# LineSensors.net
KiCad netlist of a schematic drawn in Altium Designer
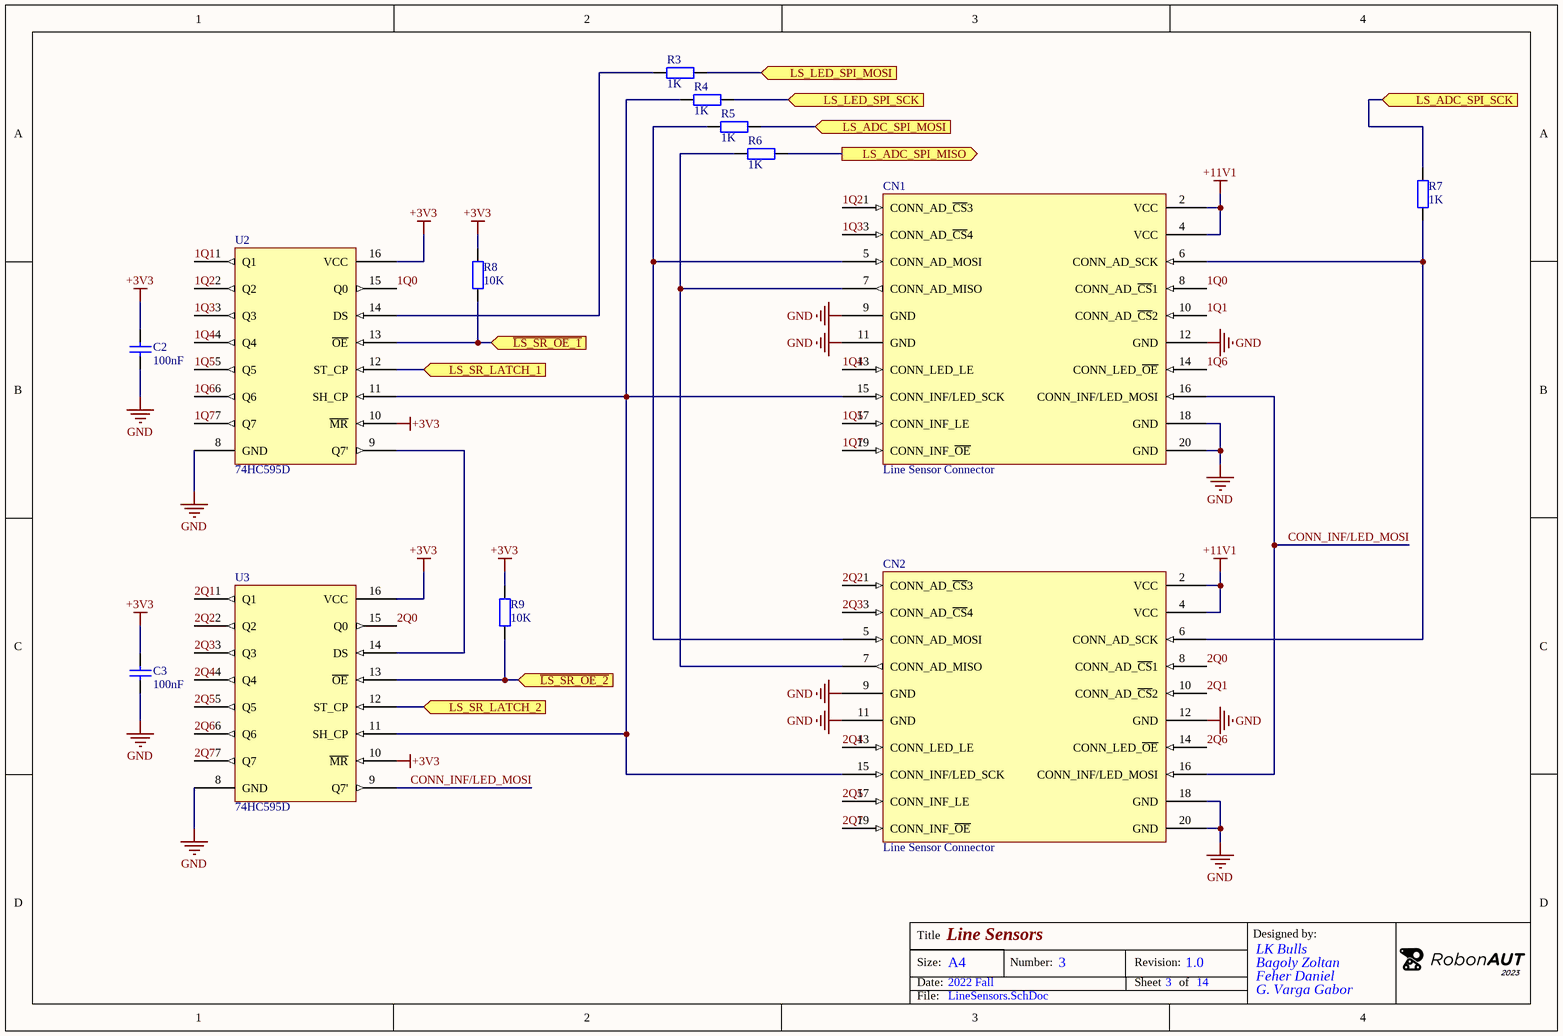
[diagram p0: LineSensors.SchDoc]

(export (version "E")
  (design (tool "Eeschema 10.0.6"))
  (components
    (comp (ref "C2")
      (value "100nF")
      (footprint "FP_0805_CAP_085")
      (description "Capacitor")
      (fields (field (name "TOLERANCE") "10%") (field (name "VOLTAGE") "50V"))
      (libsource (lib "LKBulls2023") (part "CAP"))
    )
    (comp (ref "C3")
      (value "100nF")
      (footprint "FP_0805_CAP_085")
      (description "Capacitor")
      (fields (field (name "TOLERANCE") "10%") (field (name "VOLTAGE") "50V"))
      (libsource (lib "LKBulls2023") (part "CAP"))
    )
    (comp (ref "CN1")
      (value "Line Sensor Connector")
      (footprint "CONNECTOR-20P")
      (libsource (lib "LKBulls2023") (part "Connector_Line_Sensor"))
    )
    (comp (ref "CN2")
      (value "Line Sensor Connector")
      (footprint "CONNECTOR-20P")
      (libsource (lib "LKBulls2023") (part "Connector_Line_Sensor"))
    )
    (comp (ref "R3")
      (value "1K")
      (footprint "FP_0805_RES")
      (description "Resistor")
      (fields (field (name "TOLERANCE") "5%") (field (name "POWER") "0.125W"))
      (libsource (lib "LKBulls2023") (part "RES"))
    )
    (comp (ref "R4")
      (value "1K")
      (footprint "FP_0805_RES")
      (description "Resistor")
      (fields (field (name "TOLERANCE") "5%") (field (name "POWER") "0.125W"))
      (libsource (lib "LKBulls2023") (part "RES"))
    )
    (comp (ref "R5")
      (value "1K")
      (footprint "FP_0805_RES")
      (description "Resistor")
      (fields (field (name "TOLERANCE") "5%") (field (name "POWER") "0.125W"))
      (libsource (lib "LKBulls2023") (part "RES"))
    )
    (comp (ref "R6")
      (value "1K")
      (footprint "FP_0805_RES")
      (description "Resistor")
      (fields (field (name "TOLERANCE") "5%") (field (name "POWER") "0.125W"))
      (libsource (lib "LKBulls2023") (part "RES"))
    )
    (comp (ref "R7")
      (value "1K")
      (footprint "FP_0805_RES")
      (description "Resistor")
      (fields (field (name "TOLERANCE") "5%") (field (name "POWER") "0.125W"))
      (libsource (lib "") (part "RES_1"))
    )
    (comp (ref "R8")
      (value "10K")
      (footprint "FP_0805_RES")
      (description "Resistor")
      (fields (field (name "TOLERANCE") "5%") (field (name "POWER") "0.125W"))
      (libsource (lib "") (part "RES_1"))
    )
    (comp (ref "R9")
      (value "10K")
      (footprint "FP_0805_RES")
      (description "Resistor")
      (fields (field (name "TOLERANCE") "5%") (field (name "POWER") "0.125W"))
      (libsource (lib "") (part "RES_1"))
    )
    (comp (ref "U2")
      (value "74HC595D")
      (footprint "SO16")
      (description "8-bit serial-in, serial or parallel-out shift register with output latches; 3-state")
      (libsource (lib "LKBulls2023") (part "74HC595D"))
    )
    (comp (ref "U3")
      (value "74HC595D")
      (footprint "SO16")
      (description "8-bit serial-in, serial or parallel-out shift register with output latches; 3-state")
      (libsource (lib "LKBulls2023") (part "74HC595D"))
    )
  )
  (nets
    (net (code "1") (name "+3V3") (class "Default")
      (node (ref "C2") (pin "2") (pinfunction "2_2") (pintype "passive"))
      (node (ref "C3") (pin "2") (pinfunction "2_2") (pintype "passive"))
      (node (ref "R8") (pin "2") (pinfunction "2_2") (pintype "passive"))
      (node (ref "R9") (pin "2") (pinfunction "2_2") (pintype "passive"))
      (node (ref "U2") (pin "10") (pinfunction "~{MR}_10") (pintype "input"))
      (node (ref "U2") (pin "16") (pinfunction "VCC_16") (pintype "passive"))
      (node (ref "U3") (pin "10") (pinfunction "~{MR}_10") (pintype "input"))
      (node (ref "U3") (pin "16") (pinfunction "VCC_16") (pintype "passive"))
    )
    (net (code "2") (name "+11V1") (class "Default")
      (node (ref "CN1") (pin "2") (pinfunction "VCC_2") (pintype "power_in"))
      (node (ref "CN1") (pin "4") (pinfunction "VCC_4") (pintype "power_in"))
      (node (ref "CN2") (pin "2") (pinfunction "VCC_2") (pintype "power_in"))
      (node (ref "CN2") (pin "4") (pinfunction "VCC_4") (pintype "power_in"))
    )
    (net (code "3") (name "/1Q0") (class "Default")
      (node (ref "CN1") (pin "8") (pinfunction "CONN_AD_~{CS}1_8") (pintype "input"))
      (node (ref "U2") (pin "15") (pinfunction "Q0_15") (pintype "output"))
    )
    (net (code "4") (name "/1Q1") (class "Default")
      (node (ref "CN1") (pin "10") (pinfunction "CONN_AD_~{CS}2_10") (pintype "input"))
      (node (ref "U2") (pin "1") (pinfunction "Q1_1") (pintype "output"))
    )
    (net (code "5") (name "/1Q2") (class "Default")
      (node (ref "CN1") (pin "1") (pinfunction "CONN_AD_~{CS}3_1") (pintype "input"))
      (node (ref "U2") (pin "2") (pinfunction "Q2_2") (pintype "output"))
    )
    (net (code "6") (name "/1Q3") (class "Default")
      (node (ref "CN1") (pin "3") (pinfunction "CONN_AD_~{CS}4_3") (pintype "input"))
      (node (ref "U2") (pin "3") (pinfunction "Q3_3") (pintype "output"))
    )
    (net (code "7") (name "/1Q4") (class "Default")
      (node (ref "CN1") (pin "13") (pinfunction "CONN_LED_LE_13") (pintype "input"))
      (node (ref "U2") (pin "4") (pinfunction "Q4_4") (pintype "output"))
    )
    (net (code "8") (name "/1Q5") (class "Default")
      (node (ref "CN1") (pin "17") (pinfunction "CONN_INF_LE_17") (pintype "input"))
      (node (ref "U2") (pin "5") (pinfunction "Q5_5") (pintype "output"))
    )
    (net (code "9") (name "/1Q6") (class "Default")
      (node (ref "CN1") (pin "14") (pinfunction "CONN_LED_~{OE}_14") (pintype "input"))
      (node (ref "U2") (pin "6") (pinfunction "Q6_6") (pintype "output"))
    )
    (net (code "10") (name "/1Q7") (class "Default")
      (node (ref "CN1") (pin "19") (pinfunction "CONN_INF_~{OE}_19") (pintype "input"))
      (node (ref "U2") (pin "7") (pinfunction "Q7_7") (pintype "output"))
    )
    (net (code "11") (name "/2Q0") (class "Default")
      (node (ref "CN2") (pin "8") (pinfunction "CONN_AD_~{CS}1_8") (pintype "input"))
      (node (ref "U3") (pin "15") (pinfunction "Q0_15") (pintype "output"))
    )
    (net (code "12") (name "/2Q1") (class "Default")
      (node (ref "CN2") (pin "10") (pinfunction "CONN_AD_~{CS}2_10") (pintype "input"))
      (node (ref "U3") (pin "1") (pinfunction "Q1_1") (pintype "output"))
    )
    (net (code "13") (name "/2Q2") (class "Default")
      (node (ref "CN2") (pin "1") (pinfunction "CONN_AD_~{CS}3_1") (pintype "input"))
      (node (ref "U3") (pin "2") (pinfunction "Q2_2") (pintype "output"))
    )
    (net (code "14") (name "/2Q3") (class "Default")
      (node (ref "CN2") (pin "3") (pinfunction "CONN_AD_~{CS}4_3") (pintype "input"))
      (node (ref "U3") (pin "3") (pinfunction "Q3_3") (pintype "output"))
    )
    (net (code "15") (name "/2Q4") (class "Default")
      (node (ref "CN2") (pin "13") (pinfunction "CONN_LED_LE_13") (pintype "input"))
      (node (ref "U3") (pin "4") (pinfunction "Q4_4") (pintype "output"))
    )
    (net (code "16") (name "/2Q5") (class "Default")
      (node (ref "CN2") (pin "17") (pinfunction "CONN_INF_LE_17") (pintype "input"))
      (node (ref "U3") (pin "5") (pinfunction "Q5_5") (pintype "output"))
    )
    (net (code "17") (name "/2Q6") (class "Default")
      (node (ref "CN2") (pin "14") (pinfunction "CONN_LED_~{OE}_14") (pintype "input"))
      (node (ref "U3") (pin "6") (pinfunction "Q6_6") (pintype "output"))
    )
    (net (code "18") (name "/2Q7") (class "Default")
      (node (ref "CN2") (pin "19") (pinfunction "CONN_INF_~{OE}_19") (pintype "input"))
      (node (ref "U3") (pin "7") (pinfunction "Q7_7") (pintype "output"))
    )
    (net (code "19") (name "/CONN_INF{slash}LED_MOSI") (class "Default")
      (node (ref "CN1") (pin "16") (pinfunction "CONN_INF/LED_MOSI_16") (pintype "input"))
      (node (ref "CN2") (pin "16") (pinfunction "CONN_INF/LED_MOSI_16") (pintype "input"))
      (node (ref "U3") (pin "9") (pinfunction "Q7'_9") (pintype "output"))
    )
    (net (code "20") (name "/LS_ADC_SPI_MISO") (class "Default")
      (node (ref "R6") (pin "2") (pinfunction "2_2") (pintype "passive"))
    )
    (net (code "21") (name "/LS_ADC_SPI_MOSI") (class "Default")
      (node (ref "R5") (pin "2") (pinfunction "2_2") (pintype "passive"))
    )
    (net (code "22") (name "/LS_ADC_SPI_SCK") (class "Default")
      (node (ref "R7") (pin "2") (pinfunction "2_2") (pintype "passive"))
    )
    (net (code "23") (name "/LS_LED_SPI_MOSI") (class "Default")
      (node (ref "R3") (pin "2") (pinfunction "2_2") (pintype "passive"))
    )
    (net (code "24") (name "/LS_LED_SPI_SCK") (class "Default")
      (node (ref "R4") (pin "2") (pinfunction "2_2") (pintype "passive"))
    )
    (net (code "25") (name "/LS_SR_LATCH_1") (class "Default")
      (node (ref "U2") (pin "12") (pinfunction "ST_CP_12") (pintype "input"))
    )
    (net (code "26") (name "/LS_SR_LATCH_2") (class "Default")
      (node (ref "U3") (pin "12") (pinfunction "ST_CP_12") (pintype "input"))
    )
    (net (code "27") (name "/~{LS_SR_OE_1}") (class "Default")
      (node (ref "R8") (pin "1") (pinfunction "1_1") (pintype "passive"))
      (node (ref "U2") (pin "13") (pinfunction "~{OE}_13") (pintype "input"))
    )
    (net (code "28") (name "/~{LS_SR_OE_2}") (class "Default")
      (node (ref "R9") (pin "1") (pinfunction "1_1") (pintype "passive"))
      (node (ref "U3") (pin "13") (pinfunction "~{OE}_13") (pintype "input"))
    )
    (net (code "29") (name "GND") (class "Default")
      (node (ref "C2") (pin "1") (pinfunction "1_1") (pintype "passive"))
      (node (ref "C3") (pin "1") (pinfunction "1_1") (pintype "passive"))
      (node (ref "CN1") (pin "11") (pinfunction "GND_11") (pintype "passive"))
      (node (ref "CN1") (pin "12") (pinfunction "GND_12") (pintype "passive"))
      (node (ref "CN1") (pin "18") (pinfunction "GND_18") (pintype "passive"))
      (node (ref "CN1") (pin "20") (pinfunction "GND_20") (pintype "passive"))
      (node (ref "CN1") (pin "9") (pinfunction "GND_9") (pintype "passive"))
      (node (ref "CN2") (pin "11") (pinfunction "GND_11") (pintype "passive"))
      (node (ref "CN2") (pin "12") (pinfunction "GND_12") (pintype "passive"))
      (node (ref "CN2") (pin "18") (pinfunction "GND_18") (pintype "passive"))
      (node (ref "CN2") (pin "20") (pinfunction "GND_20") (pintype "passive"))
      (node (ref "CN2") (pin "9") (pinfunction "GND_9") (pintype "passive"))
      (node (ref "U2") (pin "8") (pinfunction "GND_8") (pintype "passive"))
      (node (ref "U3") (pin "8") (pinfunction "GND_8") (pintype "passive"))
    )
    (net (code "30") (name "Net-(CN1-CONN_AD_MISO)") (class "Default")
      (node (ref "CN1") (pin "7") (pinfunction "CONN_AD_MISO_7") (pintype "output"))
      (node (ref "CN2") (pin "7") (pinfunction "CONN_AD_MISO_7") (pintype "output"))
      (node (ref "R6") (pin "1") (pinfunction "1_1") (pintype "passive"))
    )
    (net (code "31") (name "Net-(CN1-CONN_AD_MOSI)") (class "Default")
      (node (ref "CN1") (pin "5") (pinfunction "CONN_AD_MOSI_5") (pintype "input"))
      (node (ref "CN2") (pin "5") (pinfunction "CONN_AD_MOSI_5") (pintype "input"))
      (node (ref "R5") (pin "1") (pinfunction "1_1") (pintype "passive"))
    )
    (net (code "32") (name "Net-(CN1-CONN_AD_SCK)") (class "Default")
      (node (ref "CN1") (pin "6") (pinfunction "CONN_AD_SCK_6") (pintype "input"))
      (node (ref "CN2") (pin "6") (pinfunction "CONN_AD_SCK_6") (pintype "input"))
      (node (ref "R7") (pin "1") (pinfunction "1_1") (pintype "passive"))
    )
    (net (code "33") (name "Net-(CN1-CONN_INF{slash}LED_SCK)") (class "Default")
      (node (ref "CN1") (pin "15") (pinfunction "CONN_INF/LED_SCK_15") (pintype "input"))
      (node (ref "CN2") (pin "15") (pinfunction "CONN_INF/LED_SCK_15") (pintype "input"))
      (node (ref "R4") (pin "1") (pinfunction "1_1") (pintype "passive"))
      (node (ref "U2") (pin "11") (pinfunction "SH_CP_11") (pintype "input"))
      (node (ref "U3") (pin "11") (pinfunction "SH_CP_11") (pintype "input"))
    )
    (net (code "34") (name "Net-(U2-DS)") (class "Default")
      (node (ref "R3") (pin "1") (pinfunction "1_1") (pintype "passive"))
      (node (ref "U2") (pin "14") (pinfunction "DS_14") (pintype "input"))
    )
    (net (code "35") (name "Net-(U2-Q7')") (class "Default")
      (node (ref "U2") (pin "9") (pinfunction "Q7'_9") (pintype "output"))
      (node (ref "U3") (pin "14") (pinfunction "DS_14") (pintype "input"))
    )
  )
)
